# Schematic.net
KiCad netlist of a schematic drawn in Altium Designer
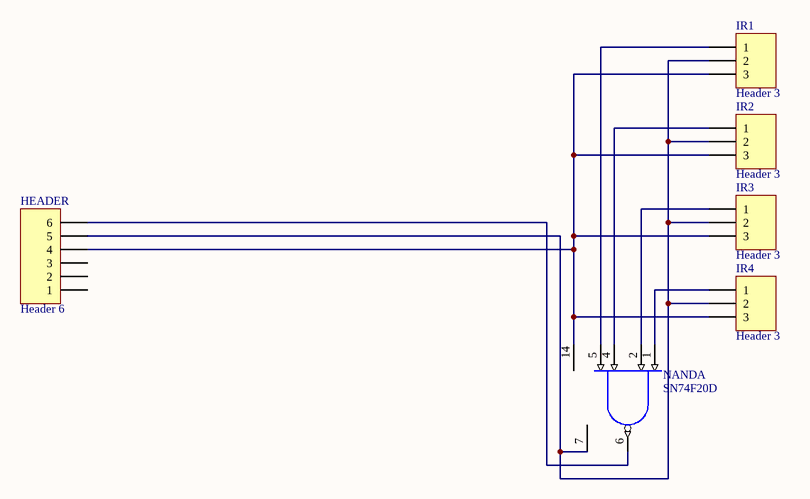
[diagram p0: Schematic.SchDoc]

(export (version "E")
  (design (tool "Eeschema 10.0.6"))
  (components
    (comp (ref "HEADER")
      (value "Header 6")
      (footprint "HDR1X6")
      (description "Header, 6-Pin")
      (fields (field (name "PUBLISHER") "Altium Limited"))
      (libsource (lib "Miscellaneous Connectors") (part "Header 6"))
    )
    (comp (ref "IR1")
      (value "Header 3")
      (footprint "HDR1X3")
      (description "Header, 3-Pin")
      (fields (field (name "PUBLISHER") "Altium Limited"))
      (libsource (lib "Miscellaneous Connectors") (part "Header 3"))
    )
    (comp (ref "IR2")
      (value "Header 3")
      (footprint "HDR1X3")
      (description "Header, 3-Pin")
      (fields (field (name "PUBLISHER") "Altium Limited"))
      (libsource (lib "Miscellaneous Connectors") (part "Header 3"))
    )
    (comp (ref "IR3")
      (value "Header 3")
      (footprint "HDR1X3")
      (description "Header, 3-Pin")
      (fields (field (name "PUBLISHER") "Altium Limited"))
      (libsource (lib "Miscellaneous Connectors") (part "Header 3"))
    )
    (comp (ref "IR4")
      (value "Header 3")
      (footprint "HDR1X3")
      (description "Header, 3-Pin")
      (fields (field (name "PUBLISHER") "Altium Limited"))
      (libsource (lib "Miscellaneous Connectors") (part "Header 3"))
    )
    (comp (ref "NAND")
      (value "SN74F20D")
      (footprint "D014_M")
      (description "Dual 4-Input Positive-NAND Gate")
      (fields (field (name "PUBLISHER") "Altium Limited"))
      (libsource (lib "TI Logic Gate 2") (part "SN74F20D"))
    )
  )
  (nets
    (net (code "1") (name "GND") (class "Default")
      (node (ref "HEADER") (pin "5") (pinfunction "5_5") (pintype "passive"))
      (node (ref "IR1") (pin "2") (pinfunction "2_2") (pintype "passive"))
      (node (ref "IR2") (pin "2") (pinfunction "2_2") (pintype "passive"))
      (node (ref "IR3") (pin "2") (pinfunction "2_2") (pintype "passive"))
      (node (ref "IR4") (pin "2") (pinfunction "2_2") (pintype "passive"))
      (node (ref "NAND") (pin "7") (pinfunction "GND_7") (pintype "power_in"))
    )
    (net (code "2") (name "Net-(NANDA-A)") (class "Default")
      (node (ref "IR4") (pin "1") (pinfunction "1_1") (pintype "passive"))
      (node (ref "NAND") (pin "1") (pinfunction "A_1") (pintype "input"))
    )
    (net (code "3") (name "Net-(NANDA-B)") (class "Default")
      (node (ref "IR3") (pin "1") (pinfunction "1_1") (pintype "passive"))
      (node (ref "NAND") (pin "2") (pinfunction "B_2") (pintype "input"))
    )
    (net (code "4") (name "Net-(NANDA-C)") (class "Default")
      (node (ref "IR2") (pin "1") (pinfunction "1_1") (pintype "passive"))
      (node (ref "NAND") (pin "4") (pinfunction "C_4") (pintype "input"))
    )
    (net (code "5") (name "Net-(NANDA-D)") (class "Default")
      (node (ref "IR1") (pin "1") (pinfunction "1_1") (pintype "passive"))
      (node (ref "NAND") (pin "5") (pinfunction "D_5") (pintype "input"))
    )
    (net (code "6") (name "Net-(NANDA-Y)") (class "Default")
      (node (ref "HEADER") (pin "6") (pinfunction "6_6") (pintype "passive"))
      (node (ref "NAND") (pin "6") (pinfunction "Y_6") (pintype "output"))
    )
    (net (code "7") (name "VCC") (class "Default")
      (node (ref "HEADER") (pin "4") (pinfunction "4_4") (pintype "passive"))
      (node (ref "IR1") (pin "3") (pinfunction "3_3") (pintype "passive"))
      (node (ref "IR2") (pin "3") (pinfunction "3_3") (pintype "passive"))
      (node (ref "IR3") (pin "3") (pinfunction "3_3") (pintype "passive"))
      (node (ref "IR4") (pin "3") (pinfunction "3_3") (pintype "passive"))
      (node (ref "NAND") (pin "14") (pinfunction "VCC_14") (pintype "power_in"))
    )
    (net (code "8") (name "unconnected-(HEADER-Pad1)") (class "Default")
      (node (ref "HEADER") (pin "1") (pinfunction "1_1") (pintype "passive"))
    )
    (net (code "9") (name "unconnected-(HEADER-Pad2)") (class "Default")
      (node (ref "HEADER") (pin "2") (pinfunction "2_2") (pintype "passive"))
    )
    (net (code "10") (name "unconnected-(HEADER-Pad3)") (class "Default")
      (node (ref "HEADER") (pin "3") (pinfunction "3_3") (pintype "passive"))
    )
  )
)
